# 09-IMC.net
KiCad netlist of a schematic drawn in Altium Designer
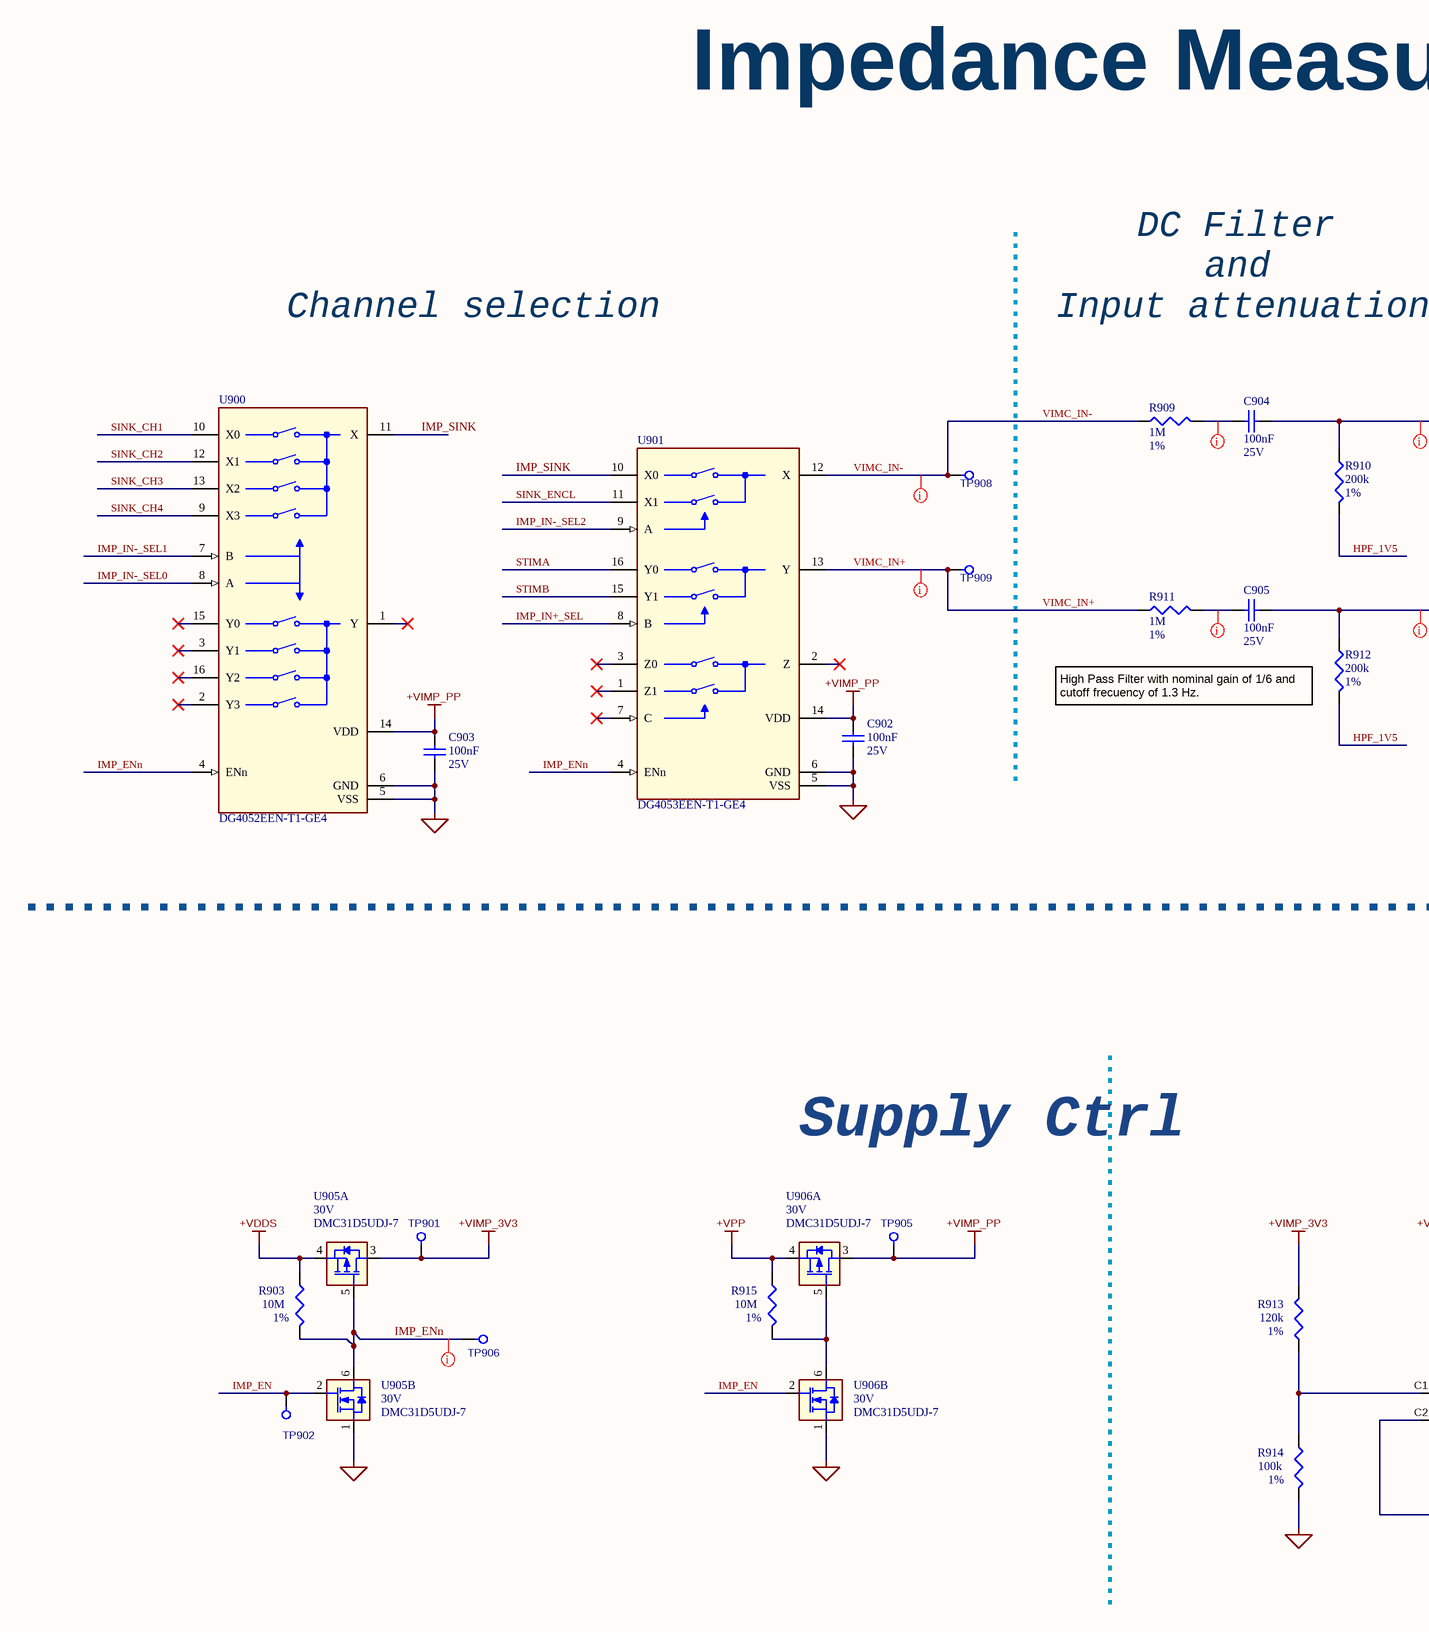
[diagram p0: 09-IMC.SchDoc, left]
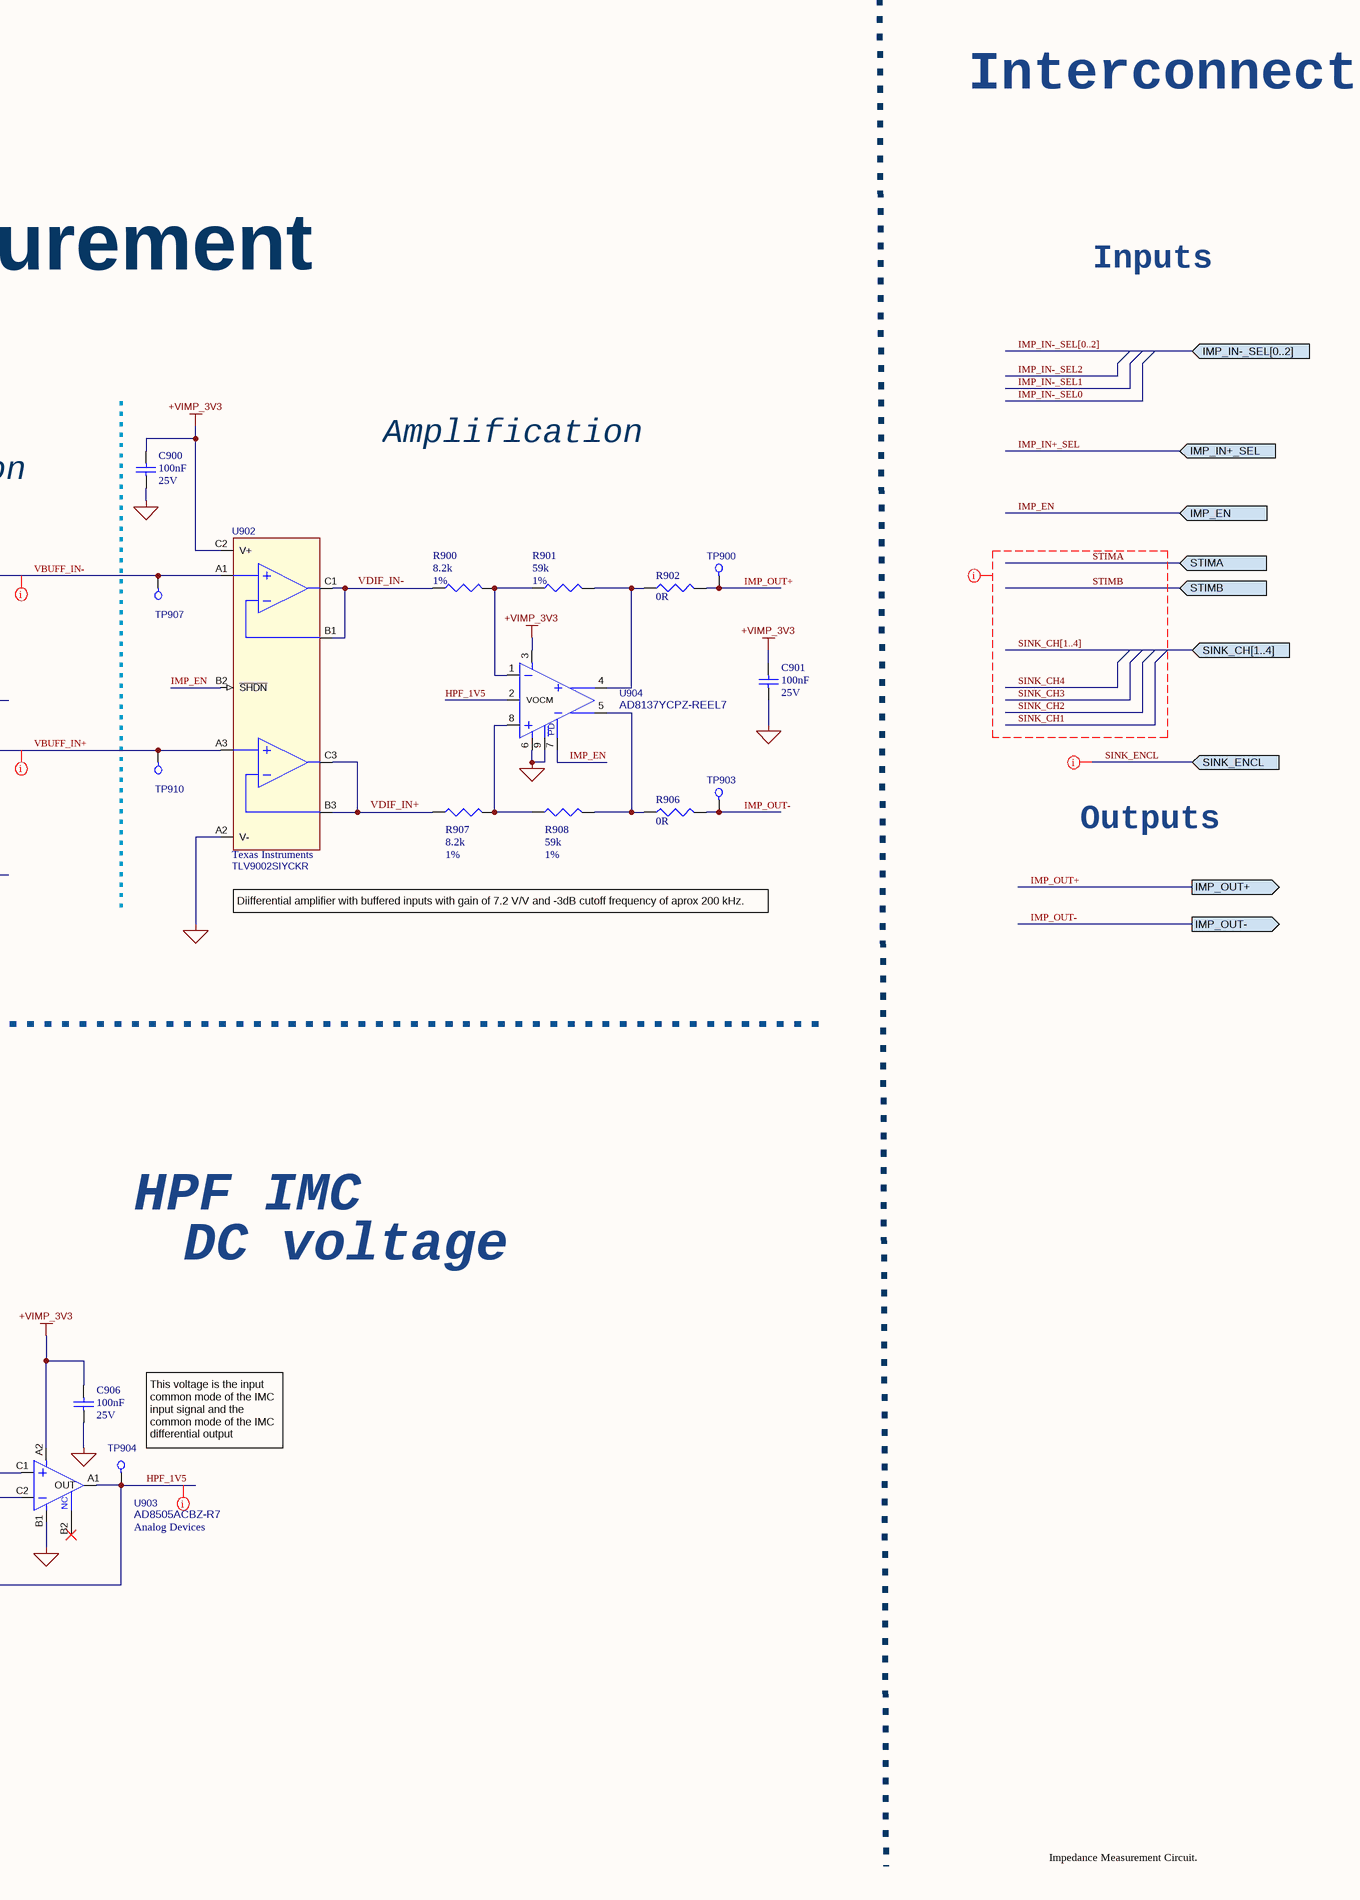
[diagram p1: 09-IMC.SchDoc, right]

(export (version "E")
  (design (tool "Eeschema 10.0.6"))
  (components
    (comp (ref "C900")
      (value "100nF")
      (footprint "C0201_C")
      (fields
        (field (name "MANUFACTURER") "Murata")
        (field (name "MANUFACTURER PART NUMBER") "GRM033R61E104KE14J")
        (field (name "RATED DC VOLTAGE (URDC)") "25V")
      )
      (libsource (lib "MP-LIBRARY") (part "GRM033R61E104KE14J"))
    )
    (comp (ref "C901")
      (value "100nF")
      (footprint "C0201_C")
      (fields
        (field (name "MANUFACTURER") "Murata")
        (field (name "MANUFACTURER PART NUMBER") "GRM033R61E104KE14J")
        (field (name "RATED DC VOLTAGE (URDC)") "25V")
      )
      (libsource (lib "MP-LIBRARY") (part "GRM033R61E104KE14J"))
    )
    (comp (ref "C902")
      (value "100nF")
      (footprint "C0201_C")
      (fields
        (field (name "MANUFACTURER") "Murata")
        (field (name "MANUFACTURER PART NUMBER") "GRM033R61E104KE14J")
        (field (name "RATED DC VOLTAGE (URDC)") "25V")
      )
      (libsource (lib "MP-LIBRARY") (part "GRM033R61E104KE14J"))
    )
    (comp (ref "C903")
      (value "100nF")
      (footprint "C0201_C")
      (fields
        (field (name "MANUFACTURER") "Murata")
        (field (name "MANUFACTURER PART NUMBER") "GRM033R61E104KE14J")
        (field (name "RATED DC VOLTAGE (URDC)") "25V")
      )
      (libsource (lib "MP-LIBRARY") (part "GRM033R61E104KE14J"))
    )
    (comp (ref "C904")
      (value "100nF")
      (footprint "C0201_C")
      (fields
        (field (name "MANUFACTURER") "Murata")
        (field (name "MANUFACTURER PART NUMBER") "GRM033R61E104KE14J")
        (field (name "RATED DC VOLTAGE (URDC)") "25V")
      )
      (libsource (lib "MP-LIBRARY") (part "GRM033R61E104KE14J"))
    )
    (comp (ref "C905")
      (value "100nF")
      (footprint "C0201_C")
      (fields
        (field (name "MANUFACTURER") "Murata")
        (field (name "MANUFACTURER PART NUMBER") "GRM033R61E104KE14J")
        (field (name "RATED DC VOLTAGE (URDC)") "25V")
      )
      (libsource (lib "MP-LIBRARY") (part "GRM033R61E104KE14J"))
    )
    (comp (ref "C906")
      (value "100nF")
      (footprint "C0201_C")
      (fields
        (field (name "MANUFACTURER") "Murata")
        (field (name "MANUFACTURER PART NUMBER") "GRM033R61E104KE14J")
        (field (name "RATED DC VOLTAGE (URDC)") "25V")
      )
      (libsource (lib "MP-LIBRARY") (part "GRM033R61E104KE14J"))
    )
    (comp (ref "R900")
      (value "8.2k")
      (footprint "R0201_C")
      (fields
        (field (name "MANUFACTURER") "Vishay")
        (field (name "MANUFACTURER PART NUMBER") "CRCW02018K20FNED")
        (field (name "TOLERANCE") "1%")
        (field (name "POWER") "50mW")
      )
      (libsource (lib "MP-LIBRARY") (part "CRCW02018K20FNED"))
    )
    (comp (ref "R901")
      (value "59k")
      (footprint "R0201_C")
      (fields
        (field (name "MANUFACTURER") "Vishay")
        (field (name "MANUFACTURER PART NUMBER") "CRCW020159K0FNED")
        (field (name "TOLERANCE") "1%")
        (field (name "POWER") "50mW")
      )
      (libsource (lib "MP-LIBRARY") (part "CRCW020159K0FNED"))
    )
    (comp (ref "R902")
      (value "0R")
      (footprint "R0201_C")
      (description "Fixed Resistor, Metal Glaze/thick Film, 0.05W, 0ohm, Surface Mount, 0201")
      (fields
        (field (name "MANUFACTURER") "Vishay")
        (field (name "MANUFACTURER PART NUMBER") "CRCW02010000Z0ED")
      )
      (libsource (lib "MP-LIBRARY") (part "CRCW02010000Z0ED"))
    )
    (comp (ref "R903")
      (value "10M")
      (footprint "R0201_C")
      (fields
        (field (name "MANUFACTURER") "Vishay Draloric")
        (field (name "MANUFACTURER PART NUMBER") "CRCW020110M0FNED")
        (field (name "TOLERANCE") "1%")
        (field (name "POWER") "50mW")
      )
      (libsource (lib "MP-LIBRARY") (part "CRCW020110M0FNED"))
    )
    (comp (ref "R906")
      (value "0R")
      (footprint "R0201_C")
      (description "Fixed Resistor, Metal Glaze/thick Film, 0.05W, 0ohm, Surface Mount, 0201")
      (fields
        (field (name "MANUFACTURER") "Vishay")
        (field (name "MANUFACTURER PART NUMBER") "CRCW02010000Z0ED")
      )
      (libsource (lib "MP-LIBRARY") (part "CRCW02010000Z0ED"))
    )
    (comp (ref "R907")
      (value "8.2k")
      (footprint "R0201_C")
      (fields
        (field (name "MANUFACTURER") "Vishay")
        (field (name "MANUFACTURER PART NUMBER") "CRCW02018K20FNED")
        (field (name "TOLERANCE") "1%")
        (field (name "POWER") "50mW")
      )
      (libsource (lib "MP-LIBRARY") (part "CRCW02018K20FNED"))
    )
    (comp (ref "R908")
      (value "59k")
      (footprint "R0201_C")
      (fields
        (field (name "MANUFACTURER") "Vishay")
        (field (name "MANUFACTURER PART NUMBER") "CRCW020159K0FNED")
        (field (name "TOLERANCE") "1%")
        (field (name "POWER") "50mW")
      )
      (libsource (lib "MP-LIBRARY") (part "CRCW020159K0FNED"))
    )
    (comp (ref "R909")
      (value "1M")
      (footprint "R0201_C")
      (fields
        (field (name "MANUFACTURER") "Vishay")
        (field (name "MANUFACTURER PART NUMBER") "CRCW02011M00FNED")
        (field (name "TOLERANCE") "1%")
        (field (name "POWER") "50mW")
      )
      (libsource (lib "MP-LIBRARY") (part "CRCW02011M00FNED"))
    )
    (comp (ref "R910")
      (value "200k")
      (footprint "R0201_C")
      (fields
        (field (name "MANUFACTURER") "Vishay")
        (field (name "MANUFACTURER PART NUMBER") "CRCW0201200KFNED")
        (field (name "TOLERANCE") "1%")
        (field (name "POWER") "50mW")
      )
      (libsource (lib "MP-LIBRARY") (part "CRCW0201200KFNED"))
    )
    (comp (ref "R911")
      (value "1M")
      (footprint "R0201_C")
      (fields
        (field (name "MANUFACTURER") "Vishay")
        (field (name "MANUFACTURER PART NUMBER") "CRCW02011M00FNED")
        (field (name "TOLERANCE") "1%")
        (field (name "POWER") "50mW")
      )
      (libsource (lib "MP-LIBRARY") (part "CRCW02011M00FNED"))
    )
    (comp (ref "R912")
      (value "200k")
      (footprint "R0201_C")
      (fields
        (field (name "MANUFACTURER") "Vishay")
        (field (name "MANUFACTURER PART NUMBER") "CRCW0201200KFNED")
        (field (name "TOLERANCE") "1%")
        (field (name "POWER") "50mW")
      )
      (libsource (lib "MP-LIBRARY") (part "CRCW0201200KFNED"))
    )
    (comp (ref "R913")
      (value "120k")
      (footprint "R0201_C")
      (fields
        (field (name "MANUFACTURER") "Vishay Dale")
        (field (name "MANUFACTURER PART NUMBER") "CRCW0201120KFNED")
        (field (name "TOLERANCE") "1%")
        (field (name "POWER") "50mW")
      )
      (libsource (lib "MP-LIBRARY") (part "CRCW0201120KFNED"))
    )
    (comp (ref "R914")
      (value "100k")
      (footprint "R0201_C")
      (fields
        (field (name "MANUFACTURER") "Vishay")
        (field (name "MANUFACTURER PART NUMBER") "CRCW0201100KFNED")
        (field (name "TOLERANCE") "1%")
        (field (name "POWER") "50mW")
      )
      (libsource (lib "MP-LIBRARY") (part "CRCW0201100KFNED"))
    )
    (comp (ref "R915")
      (value "10M")
      (footprint "R0201_C")
      (fields
        (field (name "MANUFACTURER") "Vishay Draloric")
        (field (name "MANUFACTURER PART NUMBER") "CRCW020110M0FNED")
        (field (name "TOLERANCE") "1%")
        (field (name "POWER") "50mW")
      )
      (libsource (lib "MP-LIBRARY") (part "CRCW020110M0FNED"))
    )
    (comp (ref "TP900")
      (value "Test Point")
      (footprint "testpad_0.9mm")
      (description "Test pad, 0.90mm circular pad")
      (libsource (lib "MP-LIBRARY") (part "Test Point"))
    )
    (comp (ref "TP901")
      (value "Test Point")
      (footprint "testpad_0.9mm")
      (description "Test pad, 0.90mm circular pad")
      (libsource (lib "MP-LIBRARY") (part "Test Point"))
    )
    (comp (ref "TP902")
      (value "Test Point")
      (footprint "testpad_0.9mm")
      (description "Test pad, 0.90mm circular pad")
      (libsource (lib "MP-LIBRARY") (part "Test Point"))
    )
    (comp (ref "TP903")
      (value "Test Point")
      (footprint "testpad_0.9mm")
      (description "Test pad, 0.90mm circular pad")
      (libsource (lib "MP-LIBRARY") (part "Test Point"))
    )
    (comp (ref "TP904")
      (value "Test Point")
      (footprint "testpad_0.9mm")
      (description "Test pad, 0.90mm circular pad")
      (libsource (lib "MP-LIBRARY") (part "Test Point"))
    )
    (comp (ref "TP905")
      (value "Test Point")
      (footprint "testpad_0.9mm")
      (description "Test pad, 0.90mm circular pad")
      (libsource (lib "MP-LIBRARY") (part "Test Point"))
    )
    (comp (ref "TP906")
      (value "Test Point")
      (footprint "testpad_0.9mm")
      (description "Test pad, 0.90mm circular pad")
      (libsource (lib "MP-LIBRARY") (part "Test Point"))
    )
    (comp (ref "TP907")
      (value "Test Point")
      (footprint "testpad_0.9mm")
      (description "Test pad, 0.90mm circular pad")
      (libsource (lib "MP-LIBRARY") (part "Test Point"))
    )
    (comp (ref "TP908")
      (value "Test Point")
      (footprint "testpad_0.9mm")
      (description "Test pad, 0.90mm circular pad")
      (libsource (lib "MP-LIBRARY") (part "Test Point"))
    )
    (comp (ref "TP909")
      (value "Test Point")
      (footprint "testpad_0.9mm")
      (description "Test pad, 0.90mm circular pad")
      (libsource (lib "MP-LIBRARY") (part "Test Point"))
    )
    (comp (ref "TP910")
      (value "Test Point")
      (footprint "testpad_0.9mm")
      (description "Test pad, 0.90mm circular pad")
      (libsource (lib "MP-LIBRARY") (part "Test Point"))
    )
    (comp (ref "U900")
      (value "DG4052EEN-T1-GE4")
      (footprint "QFN40P180X260X60-16N-D")
      (description "2 Circuit IC Switch 4:1 78Ohm 16-miniQFN (1.8x2.6)")
      (libsource (lib "MP-LIBRARY") (part "DG4052EEN-T1-GE4"))
    )
    (comp (ref "U901")
      (value "DG4053EEN-T1-GE4")
      (footprint "QFN40P180X260X60-16N-D")
      (description "2 Circuit IC Switch 4:1 78Ohm 16-miniQFN (1.8x2.6)")
      (libsource (lib "MP-LIBRARY") (part "DG4053EEN-T1-GE4"))
    )
    (comp (ref "U902")
      (value "TLV9002SIYCKR")
      (footprint "TI_YCK0009")
      (description "Op Amp, Dual, Rail-to-Rail, 1MHz, BGA-9")
      (fields (field (name "MANUFACTURER") "Texas Instruments"))
      (libsource (lib "MP-LIBRARY") (part "TLV9002SIYCKR_b"))
    )
    (comp (ref "U903")
      (value "AD8505ACBZ-R7")
      (footprint "AD8505ACBZ-R7")
      (description "Op Amp, Rail-to-Rail, 95kHz, WLCSP-6")
      (fields (field (name "MANUFACTURER") "Analog Devices"))
      (libsource (lib "MP-LIBRARY") (part "AD8505ACBZ-R7"))
    )
    (comp (ref "U904")
      (value "AD8137YCPZ-REEL7")
      (footprint "AD_CP-8-13")
      (description "Differential Amplifier, 110 MHz, DFN-8")
      (fields (field (name "MANUFACTURER") "Analog Devices"))
      (libsource (lib "MP-LIBRARY") (part "AD8137YCPZ-REEL7"))
    )
    (comp (ref "U905")
      (value "DMC31D5UDJ-7")
      (footprint "DIODESINC_SOT-963-6")
      (description "MOSFET N/P-CH 30V 0.22A SOT963")
      (fields (field (name "MANUFACTURER") "Diodes inc.") (field (name "VDS(MAX)") "30V"))
      (libsource (lib "MP-LIBRARY") (part "DMC31D5UDJ-7"))
    )
    (comp (ref "U906")
      (value "DMC31D5UDJ-7")
      (footprint "DIODESINC_SOT-963-6")
      (description "MOSFET N/P-CH 30V 0.22A SOT963")
      (fields (field (name "MANUFACTURER") "Diodes inc.") (field (name "VDS(MAX)") "30V"))
      (libsource (lib "MP-LIBRARY") (part "DMC31D5UDJ-7"))
    )
  )
  (nets
    (net (code "1") (name "+VDDS") (class "Default")
      (node (ref "R903") (pin "1") (pinfunction "1_1") (pintype "passive"))
      (node (ref "U905") (pin "4") (pinfunction "4_4") (pintype "passive"))
    )
    (net (code "2") (name "+VIMP_3V3") (class "Default")
      (node (ref "C900") (pin "2") (pinfunction "2_2") (pintype "passive"))
      (node (ref "C901") (pin "2") (pinfunction "2_2") (pintype "passive"))
      (node (ref "C906") (pin "2") (pinfunction "2_2") (pintype "passive"))
      (node (ref "R913") (pin "2") (pinfunction "2_2") (pintype "passive"))
      (node (ref "TP901") (pin "1") (pinfunction "1_1") (pintype "passive"))
      (node (ref "U902") (pin "C2") (pinfunction "V+_C2") (pintype "power_in"))
      (node (ref "U903") (pin "A2") (pinfunction "V+_A2") (pintype "passive"))
      (node (ref "U904") (pin "3") (pinfunction "VS+_3") (pintype "power_in"))
      (node (ref "U905") (pin "3") (pinfunction "3_3") (pintype "passive"))
    )
    (net (code "3") (name "+VIMP_PP") (class "Default")
      (node (ref "C902") (pin "2") (pinfunction "2_2") (pintype "passive"))
      (node (ref "C903") (pin "2") (pinfunction "2_2") (pintype "passive"))
      (node (ref "TP905") (pin "1") (pinfunction "1_1") (pintype "passive"))
      (node (ref "U900") (pin "14") (pinfunction "VDD_14") (pintype "power_in"))
      (node (ref "U901") (pin "14") (pinfunction "VDD_14") (pintype "passive"))
      (node (ref "U906") (pin "3") (pinfunction "3_3") (pintype "passive"))
    )
    (net (code "4") (name "+VPP") (class "Default")
      (node (ref "R915") (pin "1") (pinfunction "1_1") (pintype "passive"))
      (node (ref "U906") (pin "4") (pinfunction "4_4") (pintype "passive"))
    )
    (net (code "5") (name "/HPF_1V5") (class "Default")
      (node (ref "R910") (pin "1") (pinfunction "1_1") (pintype "passive"))
      (node (ref "R912") (pin "1") (pinfunction "1_1") (pintype "passive"))
      (node (ref "TP904") (pin "1") (pinfunction "1_1") (pintype "passive"))
      (node (ref "U903") (pin "A1") (pinfunction "OUT_A1") (pintype "passive"))
      (node (ref "U903") (pin "C2") (pinfunction "IN-_C2") (pintype "passive"))
      (node (ref "U904") (pin "2") (pinfunction "VOCM_2") (pintype "passive"))
    )
    (net (code "6") (name "/IMP_EN") (class "Default")
      (node (ref "TP902") (pin "1") (pinfunction "1_1") (pintype "passive"))
      (node (ref "U902") (pin "B2") (pinfunction "~{SHDN}_B2") (pintype "input"))
      (node (ref "U904") (pin "7") (pinfunction "~{PD}_7") (pintype "passive"))
      (node (ref "U905") (pin "2") (pinfunction "2_2") (pintype "passive"))
      (node (ref "U906") (pin "2") (pinfunction "2_2") (pintype "passive"))
    )
    (net (code "7") (name "/IMP_ENn") (class "Default")
      (node (ref "R903") (pin "2") (pinfunction "2_2") (pintype "passive"))
      (node (ref "TP906") (pin "1") (pinfunction "1_1") (pintype "passive"))
      (node (ref "U900") (pin "4") (pinfunction "ENn_4") (pintype "input"))
      (node (ref "U901") (pin "4") (pinfunction "ENn_4") (pintype "input"))
      (node (ref "U905") (pin "5") (pinfunction "5_5") (pintype "passive"))
      (node (ref "U905") (pin "6") (pinfunction "6_6") (pintype "passive"))
    )
    (net (code "8") (name "/IMP_IN+_SEL") (class "Default")
      (node (ref "U901") (pin "8") (pinfunction "B_8") (pintype "input"))
    )
    (net (code "9") (name "/IMP_IN-_SEL0") (class "Default")
      (node (ref "U900") (pin "8") (pinfunction "A_8") (pintype "input"))
    )
    (net (code "10") (name "/IMP_IN-_SEL1") (class "Default")
      (node (ref "U900") (pin "7") (pinfunction "B_7") (pintype "input"))
    )
    (net (code "11") (name "/IMP_IN-_SEL2") (class "Default")
      (node (ref "U901") (pin "9") (pinfunction "A_9") (pintype "input"))
    )
    (net (code "13") (name "/IMP_OUT+") (class "Default")
      (node (ref "R902") (pin "2") (pinfunction "2_2") (pintype "passive"))
      (node (ref "TP900") (pin "1") (pinfunction "1_1") (pintype "passive"))
    )
    (net (code "14") (name "/IMP_OUT-") (class "Default")
      (node (ref "R906") (pin "2") (pinfunction "2_2") (pintype "passive"))
      (node (ref "TP903") (pin "1") (pinfunction "1_1") (pintype "passive"))
    )
    (net (code "15") (name "/IMP_SINK") (class "Default")
      (node (ref "U900") (pin "11") (pinfunction "X_11") (pintype "passive"))
      (node (ref "U901") (pin "10") (pinfunction "X0_10") (pintype "passive"))
    )
    (net (code "16") (name "/SINK_CH1") (class "Default")
      (node (ref "U900") (pin "10") (pinfunction "X0_10") (pintype "passive"))
    )
    (net (code "17") (name "/SINK_CH2") (class "Default")
      (node (ref "U900") (pin "12") (pinfunction "X1_12") (pintype "passive"))
    )
    (net (code "18") (name "/SINK_CH3") (class "Default")
      (node (ref "U900") (pin "13") (pinfunction "X2_13") (pintype "passive"))
    )
    (net (code "19") (name "/SINK_CH4") (class "Default")
      (node (ref "U900") (pin "9") (pinfunction "X3_9") (pintype "passive"))
    )
    (net (code "21") (name "/SINK_ENCL") (class "Default")
      (node (ref "U901") (pin "11") (pinfunction "X1_11") (pintype "passive"))
    )
    (net (code "22") (name "/STIMA") (class "Default")
      (node (ref "U901") (pin "16") (pinfunction "Y0_16") (pintype "passive"))
    )
    (net (code "23") (name "/STIMB") (class "Default")
      (node (ref "U901") (pin "15") (pinfunction "Y1_15") (pintype "passive"))
    )
    (net (code "24") (name "/VBUFF_IN+") (class "Default")
      (node (ref "C905") (pin "1") (pinfunction "1_1") (pintype "passive"))
      (node (ref "R912") (pin "2") (pinfunction "2_2") (pintype "passive"))
      (node (ref "TP910") (pin "1") (pinfunction "1_1") (pintype "passive"))
      (node (ref "U902") (pin "A3") (pinfunction "IN2+_A3") (pintype "passive"))
    )
    (net (code "25") (name "/VBUFF_IN-") (class "Default")
      (node (ref "C904") (pin "1") (pinfunction "1_1") (pintype "passive"))
      (node (ref "R910") (pin "2") (pinfunction "2_2") (pintype "passive"))
      (node (ref "TP907") (pin "1") (pinfunction "1_1") (pintype "passive"))
      (node (ref "U902") (pin "A1") (pinfunction "IN1+_A1") (pintype "passive"))
    )
    (net (code "26") (name "/VDIF_IN+") (class "Default")
      (node (ref "R907") (pin "1") (pinfunction "1_1") (pintype "passive"))
      (node (ref "U902") (pin "B3") (pinfunction "IN2-_B3") (pintype "passive"))
      (node (ref "U902") (pin "C3") (pinfunction "OUT2_C3") (pintype "passive"))
    )
    (net (code "27") (name "/VDIF_IN-") (class "Default")
      (node (ref "R900") (pin "1") (pinfunction "1_1") (pintype "passive"))
      (node (ref "U902") (pin "B1") (pinfunction "IN1-_B1") (pintype "passive"))
      (node (ref "U902") (pin "C1") (pinfunction "OUT1_C1") (pintype "passive"))
    )
    (net (code "28") (name "/VIMC_IN+") (class "Default")
      (node (ref "R911") (pin "2") (pinfunction "2_2") (pintype "passive"))
      (node (ref "TP909") (pin "1") (pinfunction "1_1") (pintype "passive"))
      (node (ref "U901") (pin "13") (pinfunction "Y_13") (pintype "passive"))
    )
    (net (code "29") (name "/VIMC_IN-") (class "Default")
      (node (ref "R909") (pin "2") (pinfunction "2_2") (pintype "passive"))
      (node (ref "TP908") (pin "1") (pinfunction "1_1") (pintype "passive"))
      (node (ref "U901") (pin "12") (pinfunction "X_12") (pintype "passive"))
    )
    (net (code "30") (name "GND") (class "Default")
      (node (ref "C900") (pin "1") (pinfunction "1_1") (pintype "passive"))
      (node (ref "C901") (pin "1") (pinfunction "1_1") (pintype "passive"))
      (node (ref "C902") (pin "1") (pinfunction "1_1") (pintype "passive"))
      (node (ref "C903") (pin "1") (pinfunction "1_1") (pintype "passive"))
      (node (ref "C906") (pin "1") (pinfunction "1_1") (pintype "passive"))
      (node (ref "R914") (pin "2") (pinfunction "2_2") (pintype "passive"))
      (node (ref "U900") (pin "5") (pinfunction "VSS_5") (pintype "power_in"))
      (node (ref "U900") (pin "6") (pinfunction "GND_6") (pintype "power_in"))
      (node (ref "U901") (pin "5") (pinfunction "VSS_5") (pintype "passive"))
      (node (ref "U901") (pin "6") (pinfunction "GND_6") (pintype "passive"))
      (node (ref "U902") (pin "A2") (pinfunction "V-_A2") (pintype "power_in"))
      (node (ref "U903") (pin "B1") (pinfunction "V-_B1") (pintype "power_in"))
      (node (ref "U904") (pin "6") (pinfunction "VS-_6") (pintype "power_in"))
      (node (ref "U904") (pin "9") (pinfunction "EP_9") (pintype "passive"))
      (node (ref "U905") (pin "1") (pinfunction "1_1") (pintype "passive"))
      (node (ref "U906") (pin "1") (pinfunction "1_1") (pintype "passive"))
    )
    (net (code "31") (name "Net-(C904-Pad2)") (class "Default")
      (node (ref "C904") (pin "2") (pinfunction "2_2") (pintype "passive"))
      (node (ref "R909") (pin "1") (pinfunction "1_1") (pintype "passive"))
    )
    (net (code "32") (name "Net-(C905-Pad2)") (class "Default")
      (node (ref "C905") (pin "2") (pinfunction "2_2") (pintype "passive"))
      (node (ref "R911") (pin "1") (pinfunction "1_1") (pintype "passive"))
    )
    (net (code "33") (name "Net-(R915-Pad2)") (class "Default")
      (node (ref "R915") (pin "2") (pinfunction "2_2") (pintype "passive"))
      (node (ref "U906") (pin "5") (pinfunction "5_5") (pintype "passive"))
      (node (ref "U906") (pin "6") (pinfunction "6_6") (pintype "passive"))
    )
    (net (code "34") (name "Net-(U903-IN+)") (class "Default")
      (node (ref "R913") (pin "1") (pinfunction "1_1") (pintype "passive"))
      (node (ref "R914") (pin "1") (pinfunction "1_1") (pintype "passive"))
      (node (ref "U903") (pin "C1") (pinfunction "IN+_C1") (pintype "passive"))
    )
    (net (code "35") (name "Net-(U904-+IN)") (class "Default")
      (node (ref "R907") (pin "2") (pinfunction "2_2") (pintype "passive"))
      (node (ref "R908") (pin "1") (pinfunction "1_1") (pintype "passive"))
      (node (ref "U904") (pin "8") (pinfunction "+IN_8") (pintype "passive"))
    )
    (net (code "36") (name "Net-(U904-+OUT)") (class "Default")
      (node (ref "R901") (pin "2") (pinfunction "2_2") (pintype "passive"))
      (node (ref "R902") (pin "1") (pinfunction "1_1") (pintype "passive"))
      (node (ref "U904") (pin "4") (pinfunction "+OUT_4") (pintype "passive"))
    )
    (net (code "37") (name "Net-(U904--IN)") (class "Default")
      (node (ref "R900") (pin "2") (pinfunction "2_2") (pintype "passive"))
      (node (ref "R901") (pin "1") (pinfunction "1_1") (pintype "passive"))
      (node (ref "U904") (pin "1") (pinfunction "-IN_1") (pintype "passive"))
    )
    (net (code "38") (name "Net-(U904--OUT)") (class "Default")
      (node (ref "R906") (pin "1") (pinfunction "1_1") (pintype "passive"))
      (node (ref "R908") (pin "2") (pinfunction "2_2") (pintype "passive"))
      (node (ref "U904") (pin "5") (pinfunction "-OUT_5") (pintype "passive"))
    )
    (net (code "39") (name "unconnected-(U900-Y-Pad1)") (class "Default")
      (node (ref "U900") (pin "1") (pinfunction "Y_1") (pintype "passive+no_connect"))
    )
    (net (code "40") (name "unconnected-(U900-Y0-Pad15)") (class "Default")
      (node (ref "U900") (pin "15") (pinfunction "Y0_15") (pintype "passive+no_connect"))
    )
    (net (code "41") (name "unconnected-(U900-Y1-Pad3)") (class "Default")
      (node (ref "U900") (pin "3") (pinfunction "Y1_3") (pintype "passive+no_connect"))
    )
    (net (code "42") (name "unconnected-(U900-Y2-Pad16)") (class "Default")
      (node (ref "U900") (pin "16") (pinfunction "Y2_16") (pintype "passive+no_connect"))
    )
    (net (code "43") (name "unconnected-(U900-Y3-Pad2)") (class "Default")
      (node (ref "U900") (pin "2") (pinfunction "Y3_2") (pintype "passive+no_connect"))
    )
    (net (code "44") (name "unconnected-(U901-C-Pad7)") (class "Default")
      (node (ref "U901") (pin "7") (pinfunction "C_7") (pintype "input+no_connect"))
    )
    (net (code "45") (name "unconnected-(U901-Z-Pad2)") (class "Default")
      (node (ref "U901") (pin "2") (pinfunction "Z_2") (pintype "passive+no_connect"))
    )
    (net (code "46") (name "unconnected-(U901-Z0-Pad3)") (class "Default")
      (node (ref "U901") (pin "3") (pinfunction "Z0_3") (pintype "passive+no_connect"))
    )
    (net (code "47") (name "unconnected-(U901-Z1-Pad1)") (class "Default")
      (node (ref "U901") (pin "1") (pinfunction "Z1_1") (pintype "passive+no_connect"))
    )
    (net (code "48") (name "unconnected-(U903-NC-PadB2)") (class "Default")
      (node (ref "U903") (pin "B2") (pinfunction "NC_B2") (pintype "power_in+no_connect"))
    )
  )
)
